# digital_host_for_ADS1216_main.net
KiCad netlist of a schematic drawn in Altium Designer
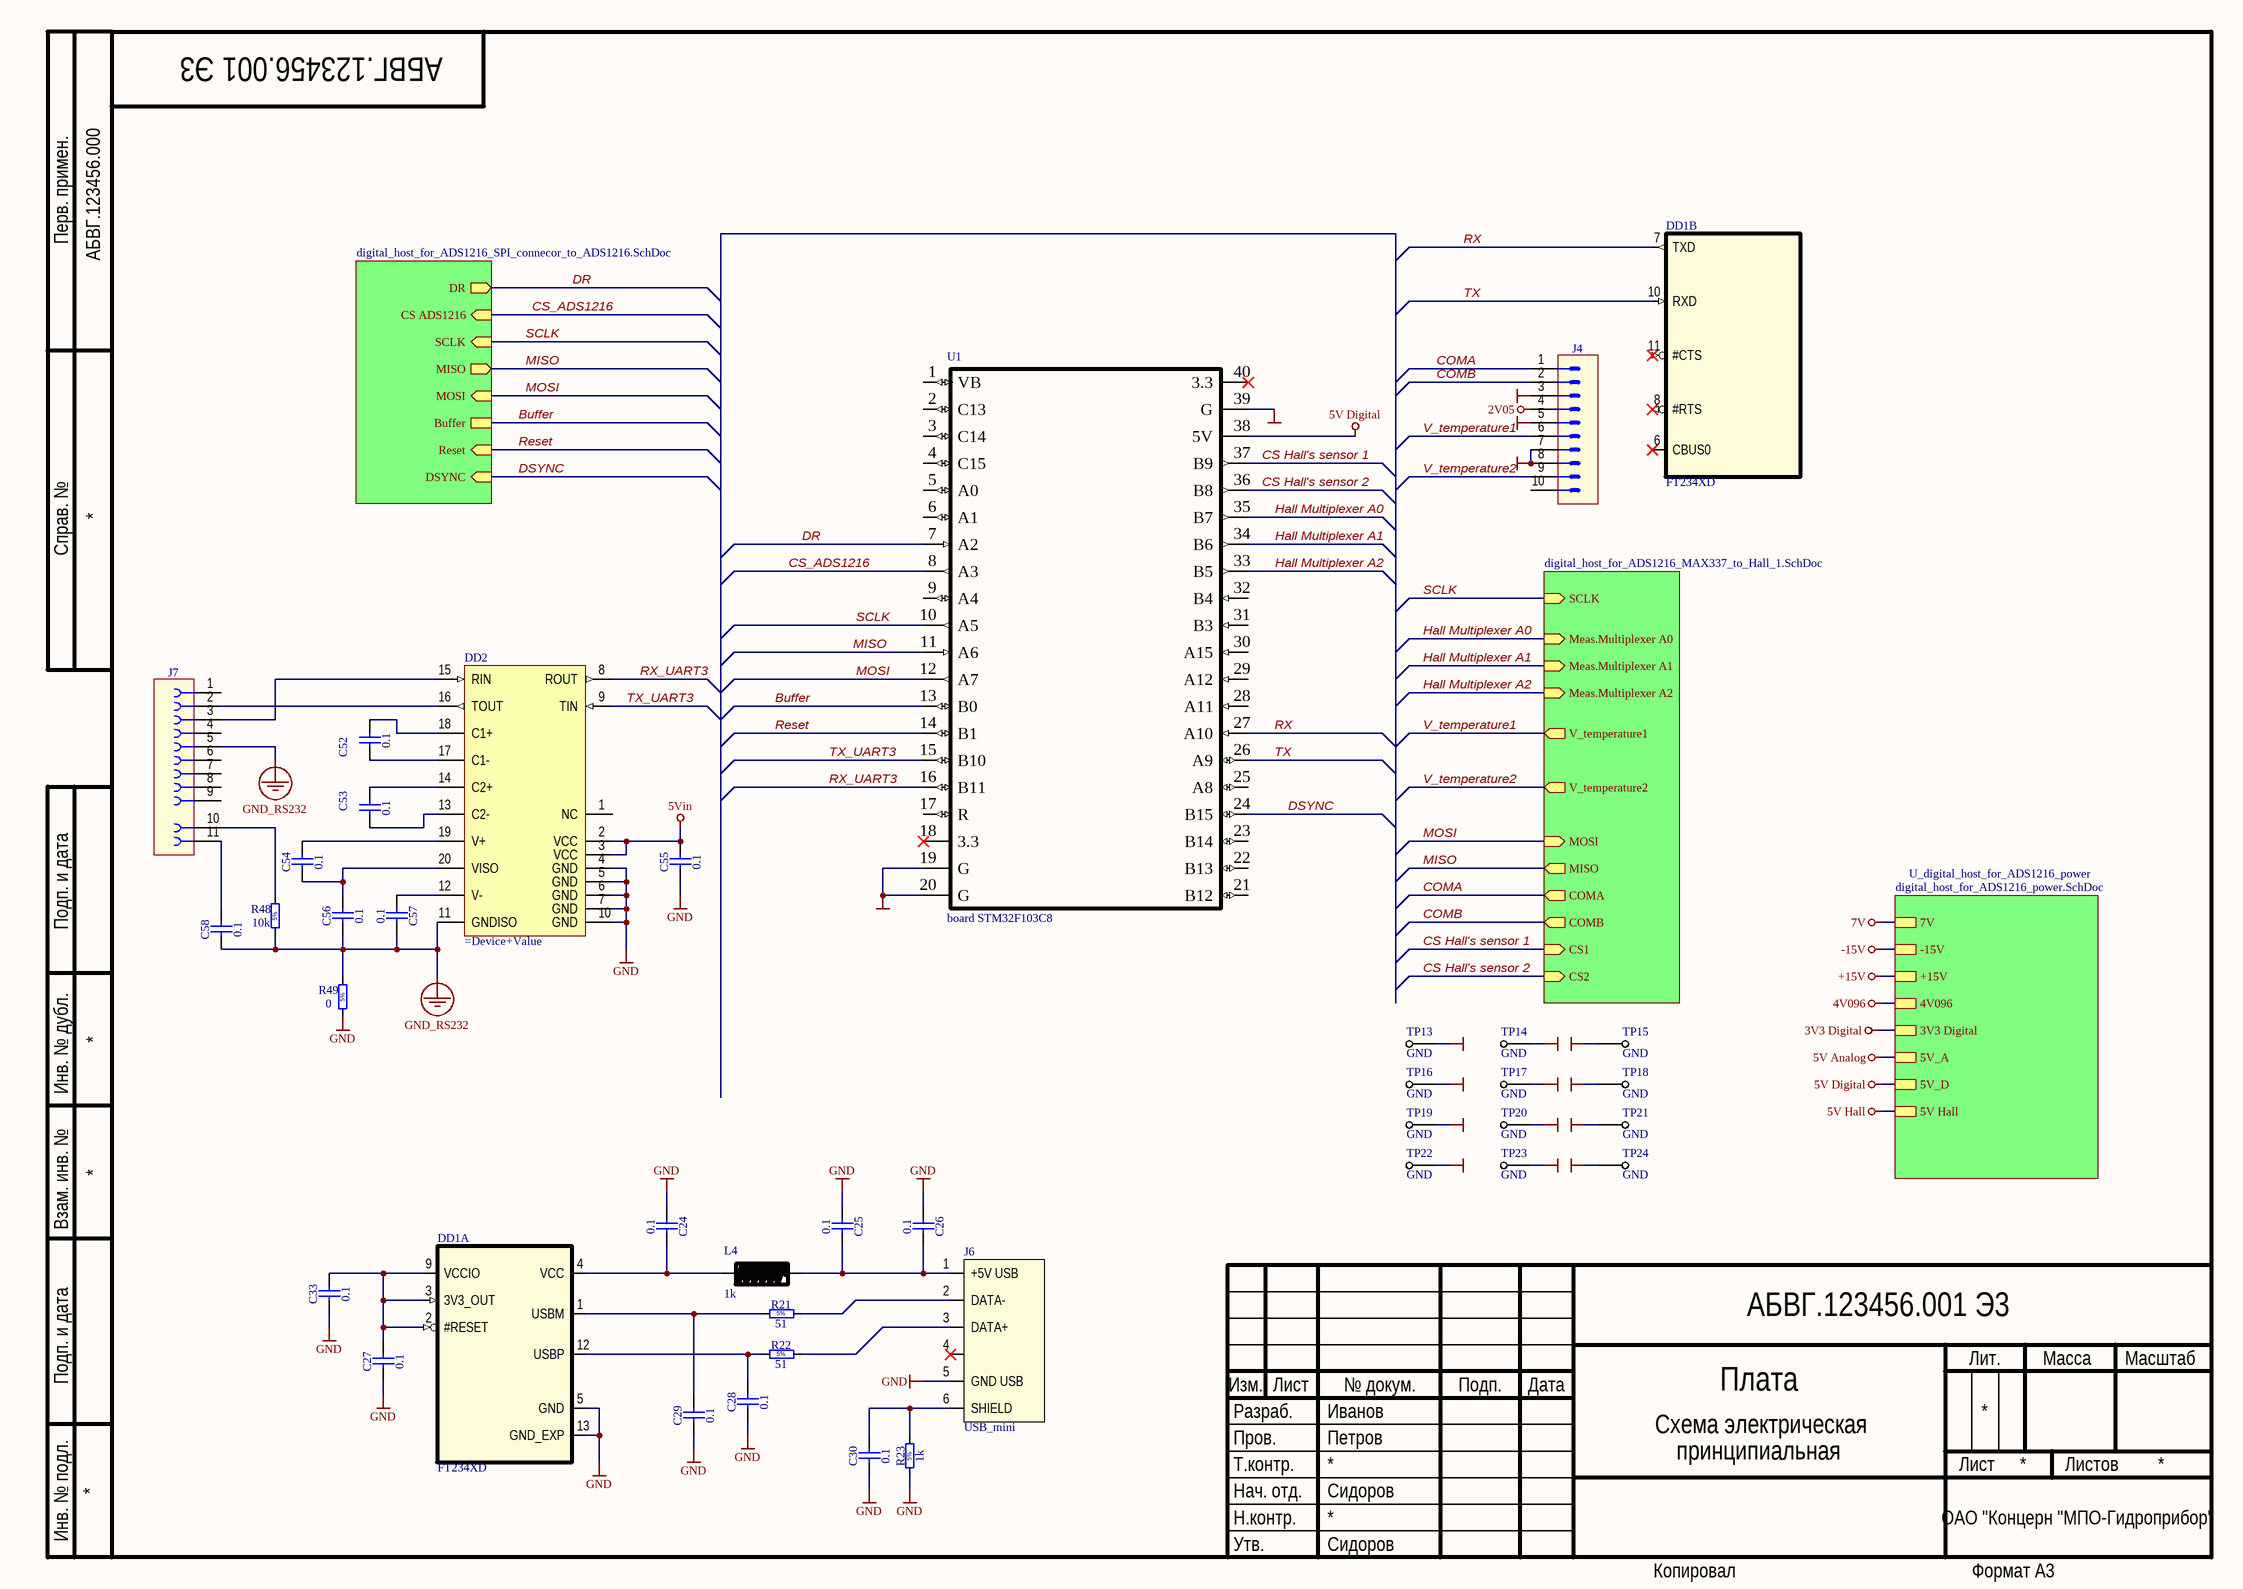
[diagram p0: digital_host_for_ADS1216_main.SchDoc]

(export (version "E")
  (design (tool "Eeschema 10.0.6"))
  (components
    (comp (ref "C24")
      (value "0.1")
      (footprint "CAPC2012X90N")
      (description "Non-polarised capacitor2012")
      (libsource (lib "schematic_hall_library") (part "Capacitor - non polarized"))
    )
    (comp (ref "C25")
      (value "0.1")
      (footprint "CAPC2012X90N")
      (description "Non-polarised capacitor2012")
      (libsource (lib "schematic_hall_library") (part "Capacitor - non polarized"))
    )
    (comp (ref "C26")
      (value "0.1")
      (footprint "CAPC2012X90N")
      (description "Non-polarised capacitor2012")
      (libsource (lib "schematic_hall_library") (part "Capacitor - non polarized"))
    )
    (comp (ref "C27")
      (value "0.1")
      (footprint "CAPC2012X90N")
      (description "Non-polarised capacitor2012")
      (libsource (lib "schematic_hall_library") (part "Capacitor - non polarized"))
    )
    (comp (ref "C28")
      (value "0.1")
      (footprint "CAPC2012X90N")
      (description "Non-polarised capacitor2012")
      (libsource (lib "schematic_hall_library") (part "Capacitor - non polarized"))
    )
    (comp (ref "C29")
      (value "0.1")
      (footprint "CAPC2012X90N")
      (description "Non-polarised capacitor2012")
      (libsource (lib "schematic_hall_library") (part "Capacitor - non polarized"))
    )
    (comp (ref "C30")
      (value "0.1")
      (footprint "CAPC2012X90N")
      (description "Non-polarised capacitor2012")
      (libsource (lib "schematic_hall_library") (part "Capacitor - non polarized"))
    )
    (comp (ref "C33")
      (value "0.1")
      (footprint "CAPC2012X90N")
      (description "Non-polarised capacitor2012")
      (libsource (lib "schematic_hall_library") (part "Capacitor - non polarized"))
    )
    (comp (ref "C52")
      (value "0.1")
      (footprint "CAPC2012X90N")
      (description "Non-polarised capacitor2012")
      (libsource (lib "schematic_hall_library") (part "Capacitor - non polarized"))
    )
    (comp (ref "C53")
      (value "0.1")
      (footprint "CAPC2012X90N")
      (description "Non-polarised capacitor2012")
      (libsource (lib "schematic_hall_library") (part "Capacitor - non polarized"))
    )
    (comp (ref "C54")
      (value "0.1")
      (footprint "CAPC2012X90N")
      (description "Non-polarised capacitor2012")
      (libsource (lib "schematic_hall_library") (part "Capacitor - non polarized"))
    )
    (comp (ref "C55")
      (value "0.1")
      (footprint "CAPC2012X90N")
      (description "Non-polarised capacitor2012")
      (libsource (lib "schematic_hall_library") (part "Capacitor - non polarized"))
    )
    (comp (ref "C56")
      (value "0.1")
      (footprint "CAPC2012X90N")
      (description "Non-polarised capacitor2012")
      (libsource (lib "schematic_hall_library") (part "Capacitor - non polarized"))
    )
    (comp (ref "C57")
      (value "0.1")
      (footprint "CAPC2012X90N")
      (description "Non-polarised capacitor2012")
      (libsource (lib "schematic_hall_library") (part "Capacitor - non polarized"))
    )
    (comp (ref "C58")
      (value "0.1")
      (footprint "CAPC2012X90N")
      (description "Non-polarised capacitor2012")
      (libsource (lib "schematic_hall_library") (part "Capacitor - non polarized"))
    )
    (comp (ref "DD1")
      (value "FT234XD")
      (footprint "DFN_12-045")
      (description "USB-UART driver")
      (libsource (lib "Integrated_Library1") (part "FT234XD"))
    )
    (comp (ref "DD2")
      (value "ADM3251")
      (footprint "footprint_hall_library:SOIC127P1032X265-20N")
      (description "Driver UART-RS232")
      (libsource (lib "schematic_hall_crossboard_1_1_library") (part "ADM3251"))
    )
    (comp (ref "J4")
      (value "~")
      (footprint "footprint_library:3M_N2510-6002RB")
      (description "Connector 10 Male")
      (libsource (lib "first_scheme.~(65)") (part "Connector 10 Male"))
    )
    (comp (ref "J6")
      (value "USB_mini")
      (footprint "TYCO_1734035-1")
      (description "Вилка  PLS 6x2.54")
      (libsource (lib "Integrated_Library1") (part "USB_mini"))
    )
    (comp (ref "J7")
      (value "~")
      (footprint "footprint_hall_library:TYCO_5747844-5")
      (description "Connector 9 Female")
      (libsource (lib "schematic_hall_library") (part "Connector 9 Female"))
    )
    (comp (ref "L4")
      (value "1k")
      (footprint "footprint_library:RESC2012X50N")
      (description "SMD Ferrite bead 0805")
      (libsource (lib "first_scheme.~(65)") (part "BLM21"))
    )
    (comp (ref "R21")
      (value "51")
      (footprint "RESC2012X70N")
      (description "Resistor - 5%")
      (fields (field (name "TOLERANCE") "5%"))
      (libsource (lib "first_scheme.~(65)") (part "Resistor - 5%"))
    )
    (comp (ref "R22")
      (value "51")
      (footprint "RESC2012X70N")
      (description "Resistor - 5%")
      (fields (field (name "TOLERANCE") "5%"))
      (libsource (lib "first_scheme.~(65)") (part "Resistor - 5%"))
    )
    (comp (ref "R23")
      (value "1k")
      (footprint "RESC2012X70N")
      (description "Resistor - 5%")
      (fields (field (name "TOLERANCE") "5%"))
      (libsource (lib "first_scheme.~(65)") (part "Resistor - 5%"))
    )
    (comp (ref "R48")
      (value "10k")
      (footprint "RESC2012X70N")
      (description "Resistor - 5%")
      (fields (field (name "TOLERANCE") "5%"))
      (libsource (lib "first_scheme.~(65)") (part "Resistor - 5%"))
    )
    (comp (ref "R49")
      (value "0")
      (footprint "RESC2012X70N")
      (description "Resistor - 5%")
      (fields (field (name "TOLERANCE") "5%"))
      (libsource (lib "first_scheme.~(65)") (part "Resistor - 5%"))
    )
    (comp (ref "TP13")
      (value "GND")
      (footprint "TP1")
      (description "Контрольная точка")
      (libsource (lib "Integrated_Library1") (part "TP"))
    )
    (comp (ref "TP14")
      (value "GND")
      (footprint "TP1")
      (description "Контрольная точка")
      (libsource (lib "Integrated_Library1") (part "TP"))
    )
    (comp (ref "TP15")
      (value "GND")
      (footprint "TP1")
      (description "Контрольная точка")
      (libsource (lib "Integrated_Library1") (part "TP"))
    )
    (comp (ref "TP16")
      (value "GND")
      (footprint "TP1")
      (description "Контрольная точка")
      (libsource (lib "Integrated_Library1") (part "TP"))
    )
    (comp (ref "TP17")
      (value "GND")
      (footprint "TP1")
      (description "Контрольная точка")
      (libsource (lib "Integrated_Library1") (part "TP"))
    )
    (comp (ref "TP18")
      (value "GND")
      (footprint "TP1")
      (description "Контрольная точка")
      (libsource (lib "Integrated_Library1") (part "TP"))
    )
    (comp (ref "TP19")
      (value "GND")
      (footprint "TP1")
      (description "Контрольная точка")
      (libsource (lib "Integrated_Library1") (part "TP"))
    )
    (comp (ref "TP20")
      (value "GND")
      (footprint "TP1")
      (description "Контрольная точка")
      (libsource (lib "Integrated_Library1") (part "TP"))
    )
    (comp (ref "TP21")
      (value "GND")
      (footprint "TP1")
      (description "Контрольная точка")
      (libsource (lib "Integrated_Library1") (part "TP"))
    )
    (comp (ref "TP22")
      (value "GND")
      (footprint "TP1")
      (description "Контрольная точка")
      (libsource (lib "Integrated_Library1") (part "TP"))
    )
    (comp (ref "TP23")
      (value "GND")
      (footprint "TP1")
      (description "Контрольная точка")
      (libsource (lib "Integrated_Library1") (part "TP"))
    )
    (comp (ref "TP24")
      (value "GND")
      (footprint "TP1")
      (description "Контрольная точка")
      (libsource (lib "Integrated_Library1") (part "TP"))
    )
    (comp (ref "U1")
      (value "board STM32F103C8")
      (footprint "footprint_library:blue_pill")
      (description "Blue Pill board")
      (libsource (lib "first_scheme.~(65)") (part "Blue Pill"))
    )
  )
  (nets
    (net (code "3") (name "/Buffer") (class "Default")
      (node (ref "U1") (pin "13") (pinfunction "B0_13") (pintype "bidirectional"))
    )
    (net (code "4") (name "/COMA") (class "Default")
      (node (ref "J4") (pin "1") (pinfunction "1_1") (pintype "passive"))
    )
    (net (code "5") (name "/COMB") (class "Default")
      (node (ref "J4") (pin "2") (pinfunction "2_2") (pintype "passive"))
    )
    (net (code "6") (name "/CS Hall's sensor 1") (class "Default")
      (node (ref "U1") (pin "37") (pinfunction "B9_37") (pintype "output"))
    )
    (net (code "7") (name "/CS Hall's sensor 2") (class "Default")
      (node (ref "U1") (pin "36") (pinfunction "B8_36") (pintype "output"))
    )
    (net (code "8") (name "/CS_ADS1216") (class "Default")
      (node (ref "U1") (pin "8") (pinfunction "A3_8") (pintype "output"))
    )
    (net (code "9") (name "/DR") (class "Default")
      (node (ref "U1") (pin "7") (pinfunction "A2_7") (pintype "input"))
    )
    (net (code "10") (name "/DSYNC") (class "Default")
      (node (ref "U1") (pin "24") (pinfunction "B15_24") (pintype "bidirectional"))
    )
    (net (code "11") (name "/Hall Multiplexer A0") (class "Default")
      (node (ref "U1") (pin "35") (pinfunction "B7_35") (pintype "output"))
    )
    (net (code "12") (name "/Hall Multiplexer A1") (class "Default")
      (node (ref "U1") (pin "34") (pinfunction "B6_34") (pintype "output"))
    )
    (net (code "13") (name "/Hall Multiplexer A2") (class "Default")
      (node (ref "U1") (pin "33") (pinfunction "B5_33") (pintype "output"))
    )
    (net (code "14") (name "/MISO") (class "Default")
      (node (ref "U1") (pin "11") (pinfunction "A6_11") (pintype "input"))
    )
    (net (code "15") (name "/MOSI") (class "Default")
      (node (ref "U1") (pin "12") (pinfunction "A7_12") (pintype "output"))
    )
    (net (code "16") (name "/RX") (class "Default")
      (node (ref "DD1") (pin "7") (pinfunction "TXD_7") (pintype "output"))
      (node (ref "U1") (pin "27") (pinfunction "A10_27") (pintype "input"))
    )
    (net (code "17") (name "/RX_UART3") (class "Default")
      (node (ref "DD2") (pin "8") (pinfunction "ROUT_8") (pintype "output"))
      (node (ref "U1") (pin "16") (pinfunction "B11_16") (pintype "bidirectional"))
    )
    (net (code "18") (name "/Reset") (class "Default")
      (node (ref "U1") (pin "14") (pinfunction "B1_14") (pintype "bidirectional"))
    )
    (net (code "19") (name "/SCLK") (class "Default")
      (node (ref "U1") (pin "10") (pinfunction "A5_10") (pintype "output"))
    )
    (net (code "20") (name "/TX") (class "Default")
      (node (ref "DD1") (pin "10") (pinfunction "RXD_10") (pintype "input"))
      (node (ref "U1") (pin "26") (pinfunction "A9_26") (pintype "bidirectional"))
    )
    (net (code "21") (name "/TX_UART3") (class "Default")
      (node (ref "DD2") (pin "9") (pinfunction "TIN_9") (pintype "input"))
      (node (ref "U1") (pin "15") (pinfunction "B10_15") (pintype "bidirectional"))
    )
    (net (code "22") (name "/V_temperature1") (class "Default")
      (node (ref "J4") (pin "6") (pinfunction "6_6") (pintype "passive"))
    )
    (net (code "23") (name "/V_temperature2") (class "Default")
      (node (ref "J4") (pin "9") (pinfunction "9_9") (pintype "passive"))
    )
    (net (code "24") (name "2V05") (class "Default")
      (node (ref "J4") (pin "4") (pinfunction "4_4") (pintype "passive"))
    )
    (net (code "28") (name "5V Digital") (class "Default")
      (node (ref "U1") (pin "38") (pinfunction "5V_38") (pintype "power_in"))
    )
    (net (code "30") (name "5Vin") (class "Default")
      (node (ref "C55") (pin "1") (pinfunction "1_1") (pintype "passive"))
      (node (ref "DD2") (pin "2") (pinfunction "VCC_2") (pintype "power_in"))
      (node (ref "DD2") (pin "3") (pinfunction "VCC_3") (pintype "power_in"))
    )
    (net (code "32") (name "GND") (class "Default")
      (node (ref "C24") (pin "1") (pinfunction "1_1") (pintype "passive"))
      (node (ref "C25") (pin "1") (pinfunction "1_1") (pintype "passive"))
      (node (ref "C26") (pin "1") (pinfunction "1_1") (pintype "passive"))
      (node (ref "C27") (pin "1") (pinfunction "1_1") (pintype "passive"))
      (node (ref "C28") (pin "1") (pinfunction "1_1") (pintype "passive"))
      (node (ref "C29") (pin "1") (pinfunction "1_1") (pintype "passive"))
      (node (ref "C30") (pin "1") (pinfunction "1_1") (pintype "passive"))
      (node (ref "C33") (pin "1") (pinfunction "1_1") (pintype "passive"))
      (node (ref "C55") (pin "2") (pinfunction "2_2") (pintype "passive"))
      (node (ref "DD1") (pin "13") (pinfunction "GND_EXP_13") (pintype "power_in"))
      (node (ref "DD1") (pin "5") (pinfunction "GND_5") (pintype "power_in"))
      (node (ref "DD2") (pin "10") (pinfunction "GND_10") (pintype "power_in"))
      (node (ref "DD2") (pin "4") (pinfunction "GND_4") (pintype "power_in"))
      (node (ref "DD2") (pin "5") (pinfunction "GND_5") (pintype "power_in"))
      (node (ref "DD2") (pin "6") (pinfunction "GND_6") (pintype "power_in"))
      (node (ref "DD2") (pin "7") (pinfunction "GND_7") (pintype "power_in"))
      (node (ref "J4") (pin "3") (pinfunction "3_3") (pintype "passive"))
      (node (ref "J4") (pin "5") (pinfunction "5_5") (pintype "passive"))
      (node (ref "J4") (pin "7") (pinfunction "7_7") (pintype "passive"))
      (node (ref "J4") (pin "8") (pinfunction "8_8") (pintype "passive"))
      (node (ref "J6") (pin "5") (pinfunction "GND_USB_5") (pintype "passive"))
      (node (ref "R23") (pin "1") (pinfunction "1_1") (pintype "passive"))
      (node (ref "R49") (pin "1") (pinfunction "1_1") (pintype "passive"))
      (node (ref "TP13") (pin "1") (pinfunction "P_1") (pintype "passive"))
      (node (ref "TP14") (pin "1") (pinfunction "P_1") (pintype "passive"))
      (node (ref "TP15") (pin "1") (pinfunction "P_1") (pintype "passive"))
      (node (ref "TP16") (pin "1") (pinfunction "P_1") (pintype "passive"))
      (node (ref "TP17") (pin "1") (pinfunction "P_1") (pintype "passive"))
      (node (ref "TP18") (pin "1") (pinfunction "P_1") (pintype "passive"))
      (node (ref "TP19") (pin "1") (pinfunction "P_1") (pintype "passive"))
      (node (ref "TP20") (pin "1") (pinfunction "P_1") (pintype "passive"))
      (node (ref "TP21") (pin "1") (pinfunction "P_1") (pintype "passive"))
      (node (ref "TP22") (pin "1") (pinfunction "P_1") (pintype "passive"))
      (node (ref "TP23") (pin "1") (pinfunction "P_1") (pintype "passive"))
      (node (ref "TP24") (pin "1") (pinfunction "P_1") (pintype "passive"))
      (node (ref "U1") (pin "19") (pinfunction "G_19") (pintype "power_in"))
      (node (ref "U1") (pin "20") (pinfunction "G_20") (pintype "power_in"))
      (node (ref "U1") (pin "39") (pinfunction "G_39") (pintype "power_in"))
    )
    (net (code "33") (name "GND_RS232") (class "Default")
      (node (ref "C56") (pin "2") (pinfunction "2_2") (pintype "passive"))
      (node (ref "C57") (pin "1") (pinfunction "1_1") (pintype "passive"))
      (node (ref "C58") (pin "2") (pinfunction "2_2") (pintype "passive"))
      (node (ref "DD2") (pin "11") (pinfunction "GNDISO_11") (pintype "power_in"))
      (node (ref "J7") (pin "5") (pinfunction "5_5") (pintype "passive"))
      (node (ref "R48") (pin "1") (pinfunction "1_1") (pintype "passive"))
      (node (ref "R49") (pin "2") (pinfunction "2_2") (pintype "passive"))
    )
    (net (code "34") (name "Net-(C58-Pad1)") (class "Default")
      (node (ref "C58") (pin "1") (pinfunction "1_1") (pintype "passive"))
      (node (ref "J7") (pin "11") (pinfunction "11_11") (pintype "passive"))
    )
    (net (code "35") (name "Net-(DD1A-#RESET)") (class "Default")
      (node (ref "C27") (pin "2") (pinfunction "2_2") (pintype "passive"))
      (node (ref "C33") (pin "2") (pinfunction "2_2") (pintype "passive"))
      (node (ref "DD1") (pin "2") (pinfunction "#RESET_2") (pintype "input"))
      (node (ref "DD1") (pin "3") (pinfunction "3V3_OUT_3") (pintype "input"))
      (node (ref "DD1") (pin "9") (pinfunction "VCCIO_9") (pintype "power_in"))
    )
    (net (code "36") (name "Net-(DD1A-USBM)") (class "Default")
      (node (ref "C29") (pin "2") (pinfunction "2_2") (pintype "passive"))
      (node (ref "DD1") (pin "1") (pinfunction "USBM_1") (pintype "bidirectional"))
      (node (ref "R21") (pin "1") (pinfunction "1_1") (pintype "passive"))
    )
    (net (code "37") (name "Net-(DD1A-USBP)") (class "Default")
      (node (ref "C28") (pin "2") (pinfunction "2_2") (pintype "passive"))
      (node (ref "DD1") (pin "12") (pinfunction "USBP_12") (pintype "bidirectional"))
      (node (ref "R22") (pin "1") (pinfunction "1_1") (pintype "passive"))
    )
    (net (code "38") (name "Net-(DD1A-VCC)") (class "Default")
      (node (ref "C24") (pin "2") (pinfunction "2_2") (pintype "passive"))
      (node (ref "DD1") (pin "4") (pinfunction "VCC_4") (pintype "power_in"))
      (node (ref "L4") (pin "1") (pinfunction "1_1") (pintype "passive"))
    )
    (net (code "39") (name "Net-(DD2-C1+)") (class "Default")
      (node (ref "C52") (pin "1") (pinfunction "1_1") (pintype "passive"))
      (node (ref "DD2") (pin "18") (pinfunction "C1+_18") (pintype "passive"))
    )
    (net (code "40") (name "Net-(DD2-C1-)") (class "Default")
      (node (ref "C52") (pin "2") (pinfunction "2_2") (pintype "passive"))
      (node (ref "DD2") (pin "17") (pinfunction "C1-_17") (pintype "passive"))
    )
    (net (code "41") (name "Net-(DD2-C2+)") (class "Default")
      (node (ref "C53") (pin "1") (pinfunction "1_1") (pintype "passive"))
      (node (ref "DD2") (pin "14") (pinfunction "C2+_14") (pintype "passive"))
    )
    (net (code "42") (name "Net-(DD2-C2-)") (class "Default")
      (node (ref "C53") (pin "2") (pinfunction "2_2") (pintype "passive"))
      (node (ref "DD2") (pin "13") (pinfunction "C2-_13") (pintype "passive"))
    )
    (net (code "43") (name "Net-(DD2-RIN)") (class "Default")
      (node (ref "DD2") (pin "15") (pinfunction "RIN_15") (pintype "input"))
      (node (ref "J7") (pin "3") (pinfunction "3_3") (pintype "passive"))
    )
    (net (code "44") (name "Net-(DD2-TOUT)") (class "Default")
      (node (ref "DD2") (pin "16") (pinfunction "TOUT_16") (pintype "output"))
      (node (ref "J7") (pin "2") (pinfunction "2_2") (pintype "passive"))
    )
    (net (code "45") (name "Net-(DD2-V+)") (class "Default")
      (node (ref "C54") (pin "1") (pinfunction "1_1") (pintype "passive"))
      (node (ref "DD2") (pin "19") (pinfunction "V+_19") (pintype "power_in"))
    )
    (net (code "46") (name "Net-(DD2-V-)") (class "Default")
      (node (ref "C57") (pin "2") (pinfunction "2_2") (pintype "passive"))
      (node (ref "DD2") (pin "12") (pinfunction "V-_12") (pintype "power_in"))
    )
    (net (code "47") (name "Net-(DD2-VISO)") (class "Default")
      (node (ref "C54") (pin "2") (pinfunction "2_2") (pintype "passive"))
      (node (ref "C56") (pin "1") (pinfunction "1_1") (pintype "passive"))
      (node (ref "DD2") (pin "20") (pinfunction "VISO_20") (pintype "power_in"))
    )
    (net (code "48") (name "Net-(J6-+5V_USB)") (class "Default")
      (node (ref "C25") (pin "2") (pinfunction "2_2") (pintype "passive"))
      (node (ref "C26") (pin "2") (pinfunction "2_2") (pintype "passive"))
      (node (ref "J6") (pin "1") (pinfunction "+5V_USB_1") (pintype "passive"))
      (node (ref "L4") (pin "2") (pinfunction "2_2") (pintype "passive"))
    )
    (net (code "49") (name "Net-(J6-DATA+)") (class "Default")
      (node (ref "J6") (pin "3") (pinfunction "DATA+_3") (pintype "passive"))
      (node (ref "R22") (pin "2") (pinfunction "2_2") (pintype "passive"))
    )
    (net (code "50") (name "Net-(J6-DATA-)") (class "Default")
      (node (ref "J6") (pin "2") (pinfunction "DATA-_2") (pintype "passive"))
      (node (ref "R21") (pin "2") (pinfunction "2_2") (pintype "passive"))
    )
    (net (code "51") (name "Net-(J6-SHIELD)") (class "Default")
      (node (ref "C30") (pin "2") (pinfunction "2_2") (pintype "passive"))
      (node (ref "J6") (pin "6") (pinfunction "SHIELD_6") (pintype "passive"))
      (node (ref "R23") (pin "2") (pinfunction "2_2") (pintype "passive"))
    )
    (net (code "52") (name "Net-(J7-Pad10)") (class "Default")
      (node (ref "J7") (pin "10") (pinfunction "10_10") (pintype "passive"))
      (node (ref "R48") (pin "2") (pinfunction "2_2") (pintype "passive"))
    )
    (net (code "53") (name "unconnected-(DD1B-#CTS-Pad11)") (class "Default")
      (node (ref "DD1") (pin "11") (pinfunction "#CTS_11") (pintype "input+no_connect"))
    )
    (net (code "54") (name "unconnected-(DD1B-#RTS-Pad8)") (class "Default")
      (node (ref "DD1") (pin "8") (pinfunction "#RTS_8") (pintype "output+no_connect"))
    )
    (net (code "55") (name "unconnected-(DD1B-CBUS0-Pad6)") (class "Default")
      (node (ref "DD1") (pin "6") (pinfunction "CBUS0_6") (pintype "bidirectional+no_connect"))
    )
    (net (code "56") (name "unconnected-(DD2-NC-Pad1)") (class "Default")
      (node (ref "DD2") (pin "1") (pinfunction "NC_1") (pintype "passive"))
    )
    (net (code "57") (name "unconnected-(J4-Pad10)") (class "Default")
      (node (ref "J4") (pin "10") (pinfunction "10_10") (pintype "passive"))
    )
    (net (code "58") (name "unconnected-(J6-Pad4)") (class "Default")
      (node (ref "J6") (pin "4") (pinfunction "4_4") (pintype "passive+no_connect"))
    )
    (net (code "59") (name "unconnected-(J7-Pad1)") (class "Default")
      (node (ref "J7") (pin "1") (pinfunction "1_1") (pintype "passive"))
    )
    (net (code "60") (name "unconnected-(J7-Pad4)") (class "Default")
      (node (ref "J7") (pin "4") (pinfunction "4_4") (pintype "passive"))
    )
    (net (code "61") (name "unconnected-(J7-Pad6)") (class "Default")
      (node (ref "J7") (pin "6") (pinfunction "6_6") (pintype "passive"))
    )
    (net (code "62") (name "unconnected-(J7-Pad7)") (class "Default")
      (node (ref "J7") (pin "7") (pinfunction "7_7") (pintype "passive"))
    )
    (net (code "63") (name "unconnected-(J7-Pad8)") (class "Default")
      (node (ref "J7") (pin "8") (pinfunction "8_8") (pintype "passive"))
    )
    (net (code "64") (name "unconnected-(J7-Pad9)") (class "Default")
      (node (ref "J7") (pin "9") (pinfunction "9_9") (pintype "passive"))
    )
    (net (code "65") (name "unconnected-(U1-3.3-Pad18)") (class "Default")
      (node (ref "U1") (pin "18") (pinfunction "3.3_18") (pintype "power_in+no_connect"))
    )
    (net (code "66") (name "unconnected-(U1-3.3-Pad40)") (class "Default")
      (node (ref "U1") (pin "40") (pinfunction "3.3_40") (pintype "power_in+no_connect"))
    )
    (net (code "67") (name "unconnected-(U1-A0-Pad5)") (class "Default")
      (node (ref "U1") (pin "5") (pinfunction "A0_5") (pintype "bidirectional"))
    )
    (net (code "68") (name "unconnected-(U1-A1-Pad6)") (class "Default")
      (node (ref "U1") (pin "6") (pinfunction "A1_6") (pintype "bidirectional"))
    )
    (net (code "69") (name "unconnected-(U1-A4-Pad9)") (class "Default")
      (node (ref "U1") (pin "9") (pinfunction "A4_9") (pintype "bidirectional"))
    )
    (net (code "70") (name "unconnected-(U1-A8-Pad25)") (class "Default")
      (node (ref "U1") (pin "25") (pinfunction "A8_25") (pintype "bidirectional"))
    )
    (net (code "71") (name "unconnected-(U1-A11-Pad28)") (class "Default")
      (node (ref "U1") (pin "28") (pinfunction "A11_28") (pintype "input"))
    )
    (net (code "72") (name "unconnected-(U1-A12-Pad29)") (class "Default")
      (node (ref "U1") (pin "29") (pinfunction "A12_29") (pintype "input"))
    )
    (net (code "73") (name "unconnected-(U1-A15-Pad30)") (class "Default")
      (node (ref "U1") (pin "30") (pinfunction "A15_30") (pintype "input"))
    )
    (net (code "74") (name "unconnected-(U1-B3-Pad31)") (class "Default")
      (node (ref "U1") (pin "31") (pinfunction "B3_31") (pintype "input"))
    )
    (net (code "75") (name "unconnected-(U1-B4-Pad32)") (class "Default")
      (node (ref "U1") (pin "32") (pinfunction "B4_32") (pintype "input"))
    )
    (net (code "76") (name "unconnected-(U1-B12-Pad21)") (class "Default")
      (node (ref "U1") (pin "21") (pinfunction "B12_21") (pintype "bidirectional"))
    )
    (net (code "77") (name "unconnected-(U1-B13-Pad22)") (class "Default")
      (node (ref "U1") (pin "22") (pinfunction "B13_22") (pintype "bidirectional"))
    )
    (net (code "78") (name "unconnected-(U1-B14-Pad23)") (class "Default")
      (node (ref "U1") (pin "23") (pinfunction "B14_23") (pintype "bidirectional"))
    )
    (net (code "79") (name "unconnected-(U1-C13-Pad2)") (class "Default")
      (node (ref "U1") (pin "2") (pinfunction "C13_2") (pintype "bidirectional"))
    )
    (net (code "80") (name "unconnected-(U1-C14-Pad3)") (class "Default")
      (node (ref "U1") (pin "3") (pinfunction "C14_3") (pintype "bidirectional"))
    )
    (net (code "81") (name "unconnected-(U1-C15-Pad4)") (class "Default")
      (node (ref "U1") (pin "4") (pinfunction "C15_4") (pintype "bidirectional"))
    )
    (net (code "82") (name "unconnected-(U1-R-Pad17)") (class "Default")
      (node (ref "U1") (pin "17") (pinfunction "R_17") (pintype "bidirectional"))
    )
    (net (code "83") (name "unconnected-(U1-VB-Pad1)") (class "Default")
      (node (ref "U1") (pin "1") (pinfunction "VB_1") (pintype "bidirectional"))
    )
  )
)
